# all_pcb.net
KiCad netlist of a schematic drawn in EasyEDA Pro
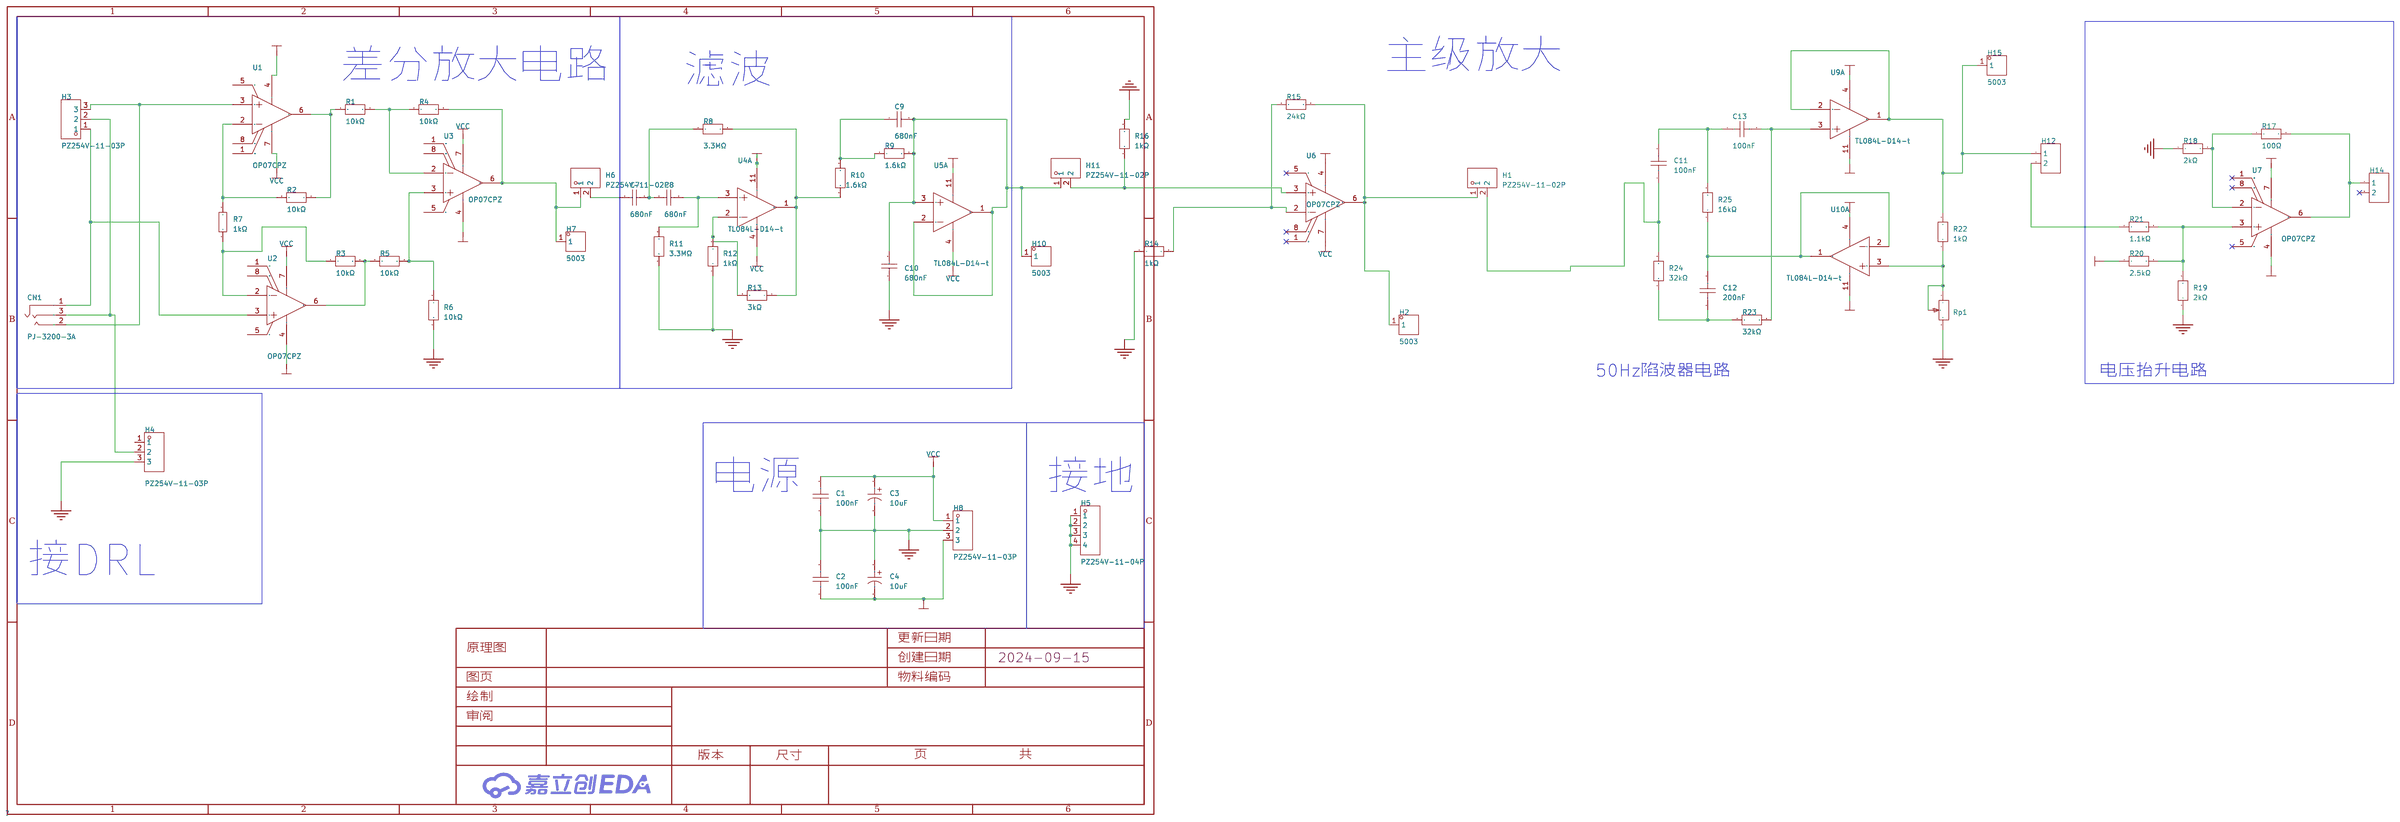
[diagram p0: schematic sheet]

(export (version "E")
  (design (tool "Eeschema 10.0.6"))
  (components
    (comp (ref "C1")
      (value "100nF")
      (footprint "easyedapro:CAP-TH_L13.0-W6.0-P10.0-D0.6")
      (description "容值:100nF;精度:±10%;电压(AC):275V;等级:X2;")
      (fields (field (name "Manufacturer Part") "1X2H410K275-11") (field (name "Manufacturer") "BM(丰明电容)"))
      (libsource (lib "easyedapro") (part "1X2H410K275-11"))
    )
    (comp (ref "C2")
      (value "100nF")
      (footprint "easyedapro:CAP-TH_L13.0-W6.0-P10.0-D0.6")
      (description "容值:100nF;精度:±10%;电压(AC):275V;等级:X2;")
      (fields (field (name "Manufacturer Part") "1X2H410K275-11") (field (name "Manufacturer") "BM(丰明电容)"))
      (libsource (lib "easyedapro") (part "1X2H410K275-11"))
    )
    (comp (ref "C3")
      (value "10uF")
      (footprint "easyedapro:CAP-TH_BD10.0-P5.00-D0.6-FD")
      (description "容值:10uF;精度:±20%;额定电压:250V;纹波电流:175mA@120Hz;等效串联电阻:-;")
      (fields
        (field (name "Manufacturer Part") "UCS2E100MPD1TD")
        (field (name "Manufacturer") "Nichicon(尼吉康)")
      )
      (libsource (lib "easyedapro") (part "UCS2E100MPD1TD"))
    )
    (comp (ref "C4")
      (value "10uF")
      (footprint "easyedapro:CAP-TH_BD10.0-P5.00-D0.6-FD")
      (description "容值:10uF;精度:±20%;额定电压:250V;纹波电流:175mA@120Hz;等效串联电阻:-;")
      (fields
        (field (name "Manufacturer Part") "UCS2E100MPD1TD")
        (field (name "Manufacturer") "Nichicon(尼吉康)")
      )
      (libsource (lib "easyedapro") (part "UCS2E100MPD1TD"))
    )
    (comp (ref "C7")
      (value "680nF")
      (footprint "easyedapro:CAP-TH_L7.5-W6.5-P5.00-D0.5")
      (description "容值:680nF;精度:±5%;额定电压:100V;工作温度:-40°C~+110°C;")
      (fields (field (name "Manufacturer Part") "PE684J2A0502") (field (name "Manufacturer") "KYET(科雅)"))
      (libsource (lib "easyedapro") (part "PE684J2A0502"))
    )
    (comp (ref "C8")
      (value "680nF")
      (footprint "easyedapro:CAP-TH_L7.5-W6.5-P5.00-D0.5")
      (description "容值:680nF;精度:±5%;额定电压:100V;工作温度:-40°C~+110°C;")
      (fields (field (name "Manufacturer Part") "PE684J2A0502") (field (name "Manufacturer") "KYET(科雅)"))
      (libsource (lib "easyedapro") (part "PE684J2A0502"))
    )
    (comp (ref "C9")
      (value "680nF")
      (footprint "easyedapro:CAP-TH_L7.5-W6.5-P5.00-D0.5")
      (description "容值:680nF;精度:±5%;额定电压:100V;工作温度:-40°C~+110°C;")
      (fields (field (name "Manufacturer Part") "PE684J2A0502") (field (name "Manufacturer") "KYET(科雅)"))
      (libsource (lib "easyedapro") (part "PE684J2A0502"))
    )
    (comp (ref "C10")
      (value "680nF")
      (footprint "easyedapro:CAP-TH_L7.5-W6.5-P5.00-D0.5")
      (description "容值:680nF;精度:±5%;额定电压:100V;工作温度:-40°C~+110°C;")
      (fields (field (name "Manufacturer Part") "PE684J2A0502") (field (name "Manufacturer") "KYET(科雅)"))
      (libsource (lib "easyedapro") (part "PE684J2A0502"))
    )
    (comp (ref "C11")
      (value "100nF")
      (footprint "easyedapro:CAP-TH_L5.1-W3.8-P5.08-D1.2")
      (description "容值:100nF;精度:±10%;额定电压:630V;温度系数:X7R;")
      (fields (field (name "Manufacturer Part") "C322C104KBR5TA") (field (name "Manufacturer") "KEMET(基美)"))
      (libsource (lib "easyedapro") (part "C322C104KBR5TA"))
    )
    (comp (ref "C12")
      (value "200nF")
      (footprint "easyedapro:CAP-TH_L18.0-W8.0-P15.00-D0.8")
      (description "容值:200nF;精度:±20%;电压(AC):305V;等级:X2;")
      (fields (field (name "Manufacturer Part") "B32922H3204M") (field (name "Manufacturer") "TDK"))
      (libsource (lib "easyedapro") (part "B32922H3204M"))
    )
    (comp (ref "C13")
      (value "100nF")
      (footprint "easyedapro:CAP-TH_L5.1-W3.8-P5.08-D1.2")
      (description "容值:100nF;精度:±10%;额定电压:630V;温度系数:X7R;")
      (fields (field (name "Manufacturer Part") "C322C104KBR5TA") (field (name "Manufacturer") "KEMET(基美)"))
      (libsource (lib "easyedapro") (part "C322C104KBR5TA"))
    )
    (comp (ref "CN1")
      (value "PJ-3200-3A")
      (footprint "easyedapro:AUDIO-TH_PJ-3200-3A")
      (description "连接器类型:3.5mm耳机座;额定电流:500mA;额定电压:30V;工作温度范围:-20°C~+70°C;")
      (fields (field (name "Manufacturer") "韩国韩荣"))
      (libsource (lib "easyedapro") (part "PJ-3200-3A"))
    )
    (comp (ref "H1")
      (value "PZ254V-11-02P")
      (footprint "easyedapro:HDR-TH_2P-P2.54-V-M")
      (fields (field (name "Manufacturer") "XFCN(兴飞)"))
      (libsource (lib "easyedapro") (part "PZ254V-11-02P"))
    )
    (comp (ref "H2")
      (value "5003")
      (footprint "easyedapro:TEST-TH_BD2.54-P1.39")
      (description "类型:测试环;全长/全高:7.62mm;工作高度:-;接触电阻:-;弹性寿命:-;额定电流:-;额定电压:-;触头材质:磷青铜;触头镀层:-;工作温度范围:-;")
      (fields (field (name "Manufacturer") "Keystone"))
      (libsource (lib "easyedapro") (part "5003"))
    )
    (comp (ref "H3")
      (value "PZ254V-11-03P")
      (footprint "easyedapro:HDR-TH_3P-P2.54-V-M")
      (fields (field (name "Manufacturer") "XFCN(兴飞)"))
      (libsource (lib "easyedapro") (part "PZ254V-11-03P_C2937625"))
    )
    (comp (ref "H4")
      (value "PZ254V-11-03P")
      (footprint "easyedapro:HDR-TH_3P-P2.54-V-M")
      (fields (field (name "Manufacturer") "XFCN(兴飞)"))
      (libsource (lib "easyedapro") (part "PZ254V-11-03P_C2937625"))
    )
    (comp (ref "H5")
      (value "PZ254V-11-04P")
      (footprint "easyedapro:HDR-TH_4P-P2.54-V-M")
      (fields (field (name "Manufacturer") "XFCN(兴飞)"))
      (libsource (lib "easyedapro") (part "PZ254V-11-04P_C2691448"))
    )
    (comp (ref "H6")
      (value "PZ254V-11-02P")
      (footprint "easyedapro:HDR-TH_2P-P2.54-V-M")
      (fields (field (name "Manufacturer") "XFCN(兴飞)"))
      (libsource (lib "easyedapro") (part "PZ254V-11-02P"))
    )
    (comp (ref "H7")
      (value "5003")
      (footprint "easyedapro:TEST-TH_BD2.54-P1.39")
      (description "类型:测试环;全长/全高:7.62mm;工作高度:-;接触电阻:-;弹性寿命:-;额定电流:-;额定电压:-;触头材质:磷青铜;触头镀层:-;工作温度范围:-;")
      (fields (field (name "Manufacturer") "Keystone"))
      (libsource (lib "easyedapro") (part "5003"))
    )
    (comp (ref "H8")
      (value "PZ254V-11-03P")
      (footprint "easyedapro:HDR-TH_3P-P2.54-V-M")
      (fields (field (name "Manufacturer") "XFCN(兴飞)"))
      (libsource (lib "easyedapro") (part "PZ254V-11-03P_C2937625"))
    )
    (comp (ref "H10")
      (value "5003")
      (footprint "easyedapro:TEST-TH_BD2.54-P1.39")
      (description "类型:测试环;全长/全高:7.62mm;工作高度:-;接触电阻:-;弹性寿命:-;额定电流:-;额定电压:-;触头材质:磷青铜;触头镀层:-;工作温度范围:-;")
      (fields (field (name "Manufacturer") "Keystone"))
      (libsource (lib "easyedapro") (part "5003"))
    )
    (comp (ref "H11")
      (value "PZ254V-11-02P")
      (footprint "easyedapro:HDR-TH_2P-P2.54-V-M")
      (fields (field (name "Manufacturer") "XFCN(兴飞)"))
      (libsource (lib "easyedapro") (part "PZ254V-11-02P"))
    )
    (comp (ref "H12")
      (value "~")
      (footprint "easyedapro:HDR-TH_2P-P2.54-V-F")
      (libsource (lib "easyedapro") (part "Header-Female-2.54_1x2"))
    )
    (comp (ref "H14")
      (value "~")
      (footprint "easyedapro:HDR-TH_2P-P2.54-V-F")
      (libsource (lib "easyedapro") (part "Header-Female-2.54_1x2"))
    )
    (comp (ref "H15")
      (value "5003")
      (footprint "easyedapro:TEST-TH_BD2.54-P1.39")
      (description "类型:测试环;全长/全高:7.62mm;工作高度:-;接触电阻:-;弹性寿命:-;额定电流:-;额定电压:-;触头材质:磷青铜;触头镀层:-;工作温度范围:-;")
      (fields (field (name "Manufacturer") "Keystone"))
      (libsource (lib "easyedapro") (part "5003"))
    )
    (comp (ref "R1")
      (value "10kΩ")
      (footprint "easyedapro:RES-TH_BD2.4-L6.3-P10.30-D0.6")
      (description "电阻类型:金属膜电阻;阻值:10kΩ;精度:±1%;功率:250mW;温度系数:±50ppm/°C;")
      (fields
        (field (name "Manufacturer Part") "RN1/4W10KFT/BA1")
        (field (name "Manufacturer") "Tyohm(幸亚电阻)")
      )
      (libsource (lib "easyedapro") (part "RN 1/4W 10K F T/B A1"))
    )
    (comp (ref "R2")
      (value "10kΩ")
      (footprint "easyedapro:RES-TH_BD2.4-L6.3-P10.30-D0.6")
      (description "电阻类型:金属膜电阻;阻值:10kΩ;精度:±1%;功率:250mW;温度系数:±50ppm/°C;")
      (fields
        (field (name "Manufacturer Part") "RN1/4W10KFT/BA1")
        (field (name "Manufacturer") "Tyohm(幸亚电阻)")
      )
      (libsource (lib "easyedapro") (part "RN 1/4W 10K F T/B A1"))
    )
    (comp (ref "R3")
      (value "10kΩ")
      (footprint "easyedapro:RES-TH_BD2.4-L6.3-P10.30-D0.6")
      (description "电阻类型:金属膜电阻;阻值:10kΩ;精度:±1%;功率:250mW;温度系数:±50ppm/°C;")
      (fields
        (field (name "Manufacturer Part") "RN1/4W10KFT/BA1")
        (field (name "Manufacturer") "Tyohm(幸亚电阻)")
      )
      (libsource (lib "easyedapro") (part "RN 1/4W 10K F T/B A1"))
    )
    (comp (ref "R4")
      (value "10kΩ")
      (footprint "easyedapro:RES-TH_BD2.4-L6.3-P10.30-D0.6")
      (description "电阻类型:金属膜电阻;阻值:10kΩ;精度:±1%;功率:250mW;温度系数:±50ppm/°C;")
      (fields
        (field (name "Manufacturer Part") "RN1/4W10KFT/BA1")
        (field (name "Manufacturer") "Tyohm(幸亚电阻)")
      )
      (libsource (lib "easyedapro") (part "RN 1/4W 10K F T/B A1"))
    )
    (comp (ref "R5")
      (value "10kΩ")
      (footprint "easyedapro:RES-TH_BD2.4-L6.3-P10.30-D0.6")
      (description "电阻类型:金属膜电阻;阻值:10kΩ;精度:±1%;功率:250mW;温度系数:±50ppm/°C;")
      (fields
        (field (name "Manufacturer Part") "RN1/4W10KFT/BA1")
        (field (name "Manufacturer") "Tyohm(幸亚电阻)")
      )
      (libsource (lib "easyedapro") (part "RN 1/4W 10K F T/B A1"))
    )
    (comp (ref "R6")
      (value "10kΩ")
      (footprint "easyedapro:RES-TH_BD2.4-L6.3-P10.30-D0.6")
      (description "电阻类型:金属膜电阻;阻值:10kΩ;精度:±1%;功率:250mW;温度系数:±50ppm/°C;")
      (fields
        (field (name "Manufacturer Part") "RN1/4W10KFT/BA1")
        (field (name "Manufacturer") "Tyohm(幸亚电阻)")
      )
      (libsource (lib "easyedapro") (part "RN 1/4W 10K F T/B A1"))
    )
    (comp (ref "R7")
      (value "1kΩ")
      (footprint "easyedapro:RES-TH_BD2.5-L6.5-P10.50-D0.6")
      (description "电阻类型:金属膜电阻;阻值:1kΩ;精度:±1%;功率:250mW;温度系数:±50ppm/°C;")
      (fields
        (field (name "Manufacturer Part") "MFR0W4F1001A50")
        (field (name "Manufacturer") "UNI-ROYAL(厚声)")
      )
      (libsource (lib "easyedapro") (part "MFR0W4F1001A50"))
    )
    (comp (ref "R8")
      (value "3.3MΩ")
      (footprint "easyedapro:RES-TH_BD2.4-L6.3-P10.30-D0.6")
      (description "电阻类型:金属膜电阻;阻值:10kΩ;精度:±1%;功率:250mW;温度系数:±50ppm/°C;")
      (fields
        (field (name "Manufacturer Part") "RN1/4W10KFT/BA1")
        (field (name "Manufacturer") "Tyohm(幸亚电阻)")
      )
      (libsource (lib "easyedapro") (part "RN 1/4W 10K F T/B A1"))
    )
    (comp (ref "R9")
      (value "1.6kΩ")
      (footprint "easyedapro:RES-TH_BD2.4-L6.3-P10.30-D0.6")
      (description "电阻类型:金属膜电阻;阻值:10kΩ;精度:±1%;功率:250mW;温度系数:±50ppm/°C;")
      (fields
        (field (name "Manufacturer Part") "RN1/4W10KFT/BA1")
        (field (name "Manufacturer") "Tyohm(幸亚电阻)")
      )
      (libsource (lib "easyedapro") (part "RN 1/4W 10K F T/B A1"))
    )
    (comp (ref "R10")
      (value "1.6kΩ")
      (footprint "easyedapro:RES-TH_BD2.4-L6.3-P10.30-D0.6")
      (description "电阻类型:金属膜电阻;阻值:10kΩ;精度:±1%;功率:250mW;温度系数:±50ppm/°C;")
      (fields
        (field (name "Manufacturer Part") "RN1/4W10KFT/BA1")
        (field (name "Manufacturer") "Tyohm(幸亚电阻)")
      )
      (libsource (lib "easyedapro") (part "RN 1/4W 10K F T/B A1"))
    )
    (comp (ref "R11")
      (value "3.3MΩ")
      (footprint "easyedapro:RES-TH_BD2.4-L6.3-P10.30-D0.6")
      (description "电阻类型:金属膜电阻;阻值:10kΩ;精度:±1%;功率:250mW;温度系数:±50ppm/°C;")
      (fields
        (field (name "Manufacturer Part") "RN1/4W10KFT/BA1")
        (field (name "Manufacturer") "Tyohm(幸亚电阻)")
      )
      (libsource (lib "easyedapro") (part "RN 1/4W 10K F T/B A1"))
    )
    (comp (ref "R12")
      (value "1kΩ")
      (footprint "easyedapro:RES-TH_BD2.4-L6.3-P10.30-D0.6")
      (description "电阻类型:金属膜电阻;阻值:10kΩ;精度:±1%;功率:250mW;温度系数:±50ppm/°C;")
      (fields
        (field (name "Manufacturer Part") "RN1/4W10KFT/BA1")
        (field (name "Manufacturer") "Tyohm(幸亚电阻)")
      )
      (libsource (lib "easyedapro") (part "RN 1/4W 10K F T/B A1"))
    )
    (comp (ref "R13")
      (value "3kΩ")
      (footprint "easyedapro:RES-TH_BD2.4-L6.3-P10.30-D0.6")
      (description "电阻类型:金属膜电阻;阻值:10kΩ;精度:±1%;功率:250mW;温度系数:±50ppm/°C;")
      (fields
        (field (name "Manufacturer Part") "RN1/4W10KFT/BA1")
        (field (name "Manufacturer") "Tyohm(幸亚电阻)")
      )
      (libsource (lib "easyedapro") (part "RN 1/4W 10K F T/B A1"))
    )
    (comp (ref "R14")
      (value "1kΩ")
      (footprint "easyedapro:RES-TH_BD2.4-L6.3-P10.30-D0.6")
      (description "电阻类型:金属膜电阻;阻值:10kΩ;精度:±1%;功率:250mW;温度系数:±50ppm/°C;")
      (fields
        (field (name "Manufacturer Part") "RN1/4W10KFT/BA1")
        (field (name "Manufacturer") "Tyohm(幸亚电阻)")
      )
      (libsource (lib "easyedapro") (part "RN 1/4W 10K F T/B A1"))
    )
    (comp (ref "R15")
      (value "24kΩ")
      (footprint "easyedapro:RES-TH_BD2.4-L6.3-P10.30-D0.6")
      (description "电阻类型:金属膜电阻;阻值:10kΩ;精度:±1%;功率:250mW;温度系数:±50ppm/°C;")
      (fields
        (field (name "Manufacturer Part") "RN1/4W10KFT/BA1")
        (field (name "Manufacturer") "Tyohm(幸亚电阻)")
      )
      (libsource (lib "easyedapro") (part "RN 1/4W 10K F T/B A1"))
    )
    (comp (ref "R16")
      (value "1kΩ")
      (footprint "easyedapro:RES-TH_BD2.4-L6.3-P10.30-D0.6")
      (description "电阻类型:金属膜电阻;阻值:10kΩ;精度:±1%;功率:250mW;温度系数:±50ppm/°C;")
      (fields
        (field (name "Manufacturer Part") "RN1/4W10KFT/BA1")
        (field (name "Manufacturer") "Tyohm(幸亚电阻)")
      )
      (libsource (lib "easyedapro") (part "RN 1/4W 10K F T/B A1"))
    )
    (comp (ref "R17")
      (value "100Ω")
      (footprint "easyedapro:RES-TH_BD3.7-L10.0-P15.00-D0.6")
      (description "电阻类型:金属膜电阻;阻值:100Ω;精度:±0.1%;功率:500mW;温度系数:±5ppm/°C;")
      (fields (field (name "Manufacturer Part") "MMFR3710B100RV9") (field (name "Manufacturer") "RESI(开步睿思)"))
      (libsource (lib "easyedapro") (part "MMFR3710B100RV9"))
    )
    (comp (ref "R18")
      (value "2kΩ")
      (footprint "easyedapro:RES-TH_BD2.3-L6.5-P10.50-D0.5")
      (description "电阻类型:金属膜电阻;阻值:2kΩ;精度:±1%;功率:250mW;温度系数:±200ppm/°C;")
      (fields (field (name "Manufacturer Part") "MF1/4W-2KΩ±1%T52") (field (name "Manufacturer") "华星机电"))
      (libsource (lib "easyedapro") (part "MF1/4W-2KΩ±1%T52"))
    )
    (comp (ref "R19")
      (value "2kΩ")
      (footprint "easyedapro:RES-TH_BD2.3-L6.5-P10.50-D0.5")
      (description "电阻类型:金属膜电阻;阻值:2kΩ;精度:±1%;功率:250mW;温度系数:±200ppm/°C;")
      (fields (field (name "Manufacturer Part") "MF1/4W-2KΩ±1%T52") (field (name "Manufacturer") "华星机电"))
      (libsource (lib "easyedapro") (part "MF1/4W-2KΩ±1%T52"))
    )
    (comp (ref "R20")
      (value "2.5kΩ")
      (footprint "easyedapro:RES-TH_BD4.6-L11.4-P15.40-D0.8")
      (description "电阻类型:绕线电阻;阻值:2.5kΩ;精度:±1%;功率:2W;温度系数:±20ppm/°C;")
      (fields (field (name "Manufacturer Part") "WHC2K5FET") (field (name "Manufacturer") "Ohmite"))
      (libsource (lib "easyedapro") (part "WHC2K5FET"))
    )
    (comp (ref "R21")
      (value "1.1kΩ")
      (footprint "easyedapro:RES-TH_BD3.3-L9.0-P13.00-D0.6")
      (description "电阻类型:金属膜电阻;阻值:1.1kΩ;精度:±5%;功率:500mW;温度系数:±300ppm/°C;")
      (fields (field (name "Manufacturer Part") "RSF-50JR-52-1K1") (field (name "Manufacturer") "YAGEO(国巨)"))
      (libsource (lib "easyedapro") (part "RSF-50JR-52-1K1"))
    )
    (comp (ref "R22")
      (value "1kΩ")
      (footprint "easyedapro:RES-TH_BD2.3-L6.5-P10.50-D0.5")
      (description "电阻类型:金属膜电阻;阻值:5.1kΩ;精度:±1%;功率:250mW;温度系数:±200ppm/°C;")
      (fields (field (name "Manufacturer Part") "MF1/4W-5.1KΩ±1%T52") (field (name "Manufacturer") "华星机电"))
      (libsource (lib "easyedapro") (part "MF1/4W-5.1KΩ±1%T52"))
    )
    (comp (ref "R23")
      (value "32kΩ")
      (footprint "easyedapro:RES-TH_BD2.4-L6.5-P10.50-D0.5")
      (description "电阻类型:金属膜电阻;阻值:32kΩ;精度:±0.1%;功率:250mW;温度系数:±25ppm/°C;")
      (fields
        (field (name "Manufacturer Part") "RNF14BTE32K0")
        (field (name "Manufacturer") "SEI(Stackpole Electronics Inc.)")
      )
      (libsource (lib "easyedapro") (part "RNF14BTE32K0"))
    )
    (comp (ref "R24")
      (value "32kΩ")
      (footprint "easyedapro:RES-TH_BD2.4-L6.5-P10.50-D0.5")
      (description "电阻类型:金属膜电阻;阻值:32kΩ;精度:±0.1%;功率:250mW;温度系数:±25ppm/°C;")
      (fields
        (field (name "Manufacturer Part") "RNF14BTE32K0")
        (field (name "Manufacturer") "SEI(Stackpole Electronics Inc.)")
      )
      (libsource (lib "easyedapro") (part "RNF14BTE32K0"))
    )
    (comp (ref "R25")
      (value "16kΩ")
      (footprint "easyedapro:RES-TH_BD3.3-L9.0-P13.00-D0.6")
      (description "电阻类型:金属膜电阻;阻值:16kΩ;精度:±5%;功率:500mW;温度系数:±300ppm/°C;")
      (fields (field (name "Manufacturer Part") "RSF-50JT-52-16K") (field (name "Manufacturer") "YAGEO(国巨)"))
      (libsource (lib "easyedapro") (part "RSF-50JT-52-16K"))
    )
    (comp (ref "Rp1")
      (value "-")
      (footprint "easyedapro:RES-ADJ-TH_3296W")
      (description "阻值:-;功率:-;")
      (fields (field (name "Manufacturer Part") "精密电位器 3296W/50欧姆"))
      (libsource (lib "easyedapro") (part "Precision potentiometer 3296W/50ohm"))
    )
    (comp (ref "U1")
      (value "OP07CPZ")
      (footprint "easyedapro:PDIP-8_L9.3-W6.4-P2.54-LS7.6-BL")
      (description "超低失调电压运算放大器")
      (fields (field (name "Manufacturer") "ADI(亚德诺)"))
      (libsource (lib "easyedapro") (part "OP07CPZ"))
    )
    (comp (ref "U2")
      (value "OP07CPZ")
      (footprint "easyedapro:PDIP-8_L9.3-W6.4-P2.54-LS7.6-BL")
      (description "超低失调电压运算放大器")
      (fields (field (name "Manufacturer") "ADI(亚德诺)"))
      (libsource (lib "easyedapro") (part "OP07CPZ"))
    )
    (comp (ref "U3")
      (value "OP07CPZ")
      (footprint "easyedapro:PDIP-8_L9.3-W6.4-P2.54-LS7.6-BL")
      (description "超低失调电压运算放大器")
      (fields (field (name "Manufacturer") "ADI(亚德诺)"))
      (libsource (lib "easyedapro") (part "OP07CPZ"))
    )
    (comp (ref "U4")
      (value "TL084L-D14-t")
      (footprint "easyedapro:PDIP-14_L19.3-W6.5-P2.54-LS7.6-BL")
      (fields (field (name "Manufacturer") "UTC(友顺)"))
      (libsource (lib "easyedapro") (part "TL084L"))
    )
    (comp (ref "U5")
      (value "TL084L-D14-t")
      (footprint "easyedapro:PDIP-14_L19.3-W6.5-P2.54-LS7.6-BL")
      (fields (field (name "Manufacturer") "UTC(友顺)"))
      (libsource (lib "easyedapro") (part "TL084L"))
    )
    (comp (ref "U6")
      (value "OP07CPZ")
      (footprint "easyedapro:PDIP-8_L9.3-W6.4-P2.54-LS7.6-BL")
      (description "超低失调电压运算放大器")
      (fields (field (name "Manufacturer") "ADI(亚德诺)"))
      (libsource (lib "easyedapro") (part "OP07CPZ"))
    )
    (comp (ref "U7")
      (value "OP07CPZ")
      (footprint "easyedapro:PDIP-8_L9.3-W6.4-P2.54-LS7.6-BL")
      (description "超低失调电压运算放大器")
      (fields (field (name "Manufacturer") "ADI(亚德诺)"))
      (libsource (lib "easyedapro") (part "OP07CPZ"))
    )
    (comp (ref "U9")
      (value "TL084L-D14-t")
      (footprint "easyedapro:PDIP-14_L19.3-W6.5-P2.54-LS7.6-BL")
      (fields (field (name "Manufacturer") "UTC(友顺)"))
      (libsource (lib "easyedapro") (part "TL084L"))
    )
    (comp (ref "U10")
      (value "TL084L-D14-t")
      (footprint "easyedapro:PDIP-14_L19.3-W6.5-P2.54-LS7.6-BL")
      (fields (field (name "Manufacturer") "UTC(友顺)"))
      (libsource (lib "easyedapro") (part "TL084L"))
    )
  )
  (nets
    (net (code "1") (name "GND") (class "Default")
      (node (ref "C1") (pin "1") (pinfunction "1_1") (pintype "unspecified"))
      (node (ref "C10") (pin "1") (pinfunction "1_1") (pintype "input"))
      (node (ref "C2") (pin "2") (pinfunction "2_2") (pintype "unspecified"))
      (node (ref "C3") (pin "2") (pinfunction "2_2") (pintype "input"))
      (node (ref "C4") (pin "1") (pinfunction "1_1") (pintype "input"))
      (node (ref "H4") (pin "3") (pinfunction "3_3") (pintype "unspecified"))
      (node (ref "H5") (pin "1") (pinfunction "1_1") (pintype "unspecified"))
      (node (ref "H5") (pin "2") (pinfunction "2_2") (pintype "unspecified"))
      (node (ref "H5") (pin "3") (pinfunction "3_3") (pintype "unspecified"))
      (node (ref "H5") (pin "4") (pinfunction "4_4") (pintype "unspecified"))
      (node (ref "H8") (pin "2") (pinfunction "2_2") (pintype "unspecified"))
      (node (ref "R11") (pin "1") (pinfunction "1_1") (pintype "unspecified"))
      (node (ref "R12") (pin "1") (pinfunction "1_1") (pintype "unspecified"))
      (node (ref "R14") (pin "1") (pinfunction "1_1") (pintype "unspecified"))
      (node (ref "R16") (pin "2") (pinfunction "2_2") (pintype "unspecified"))
      (node (ref "R18") (pin "1") (pinfunction "1_1") (pintype "unspecified"))
      (node (ref "R19") (pin "1") (pinfunction "1_1") (pintype "unspecified"))
      (node (ref "R6") (pin "1") (pinfunction "1_1") (pintype "unspecified"))
      (node (ref "Rp1") (pin "3") (pinfunction "3_3") (pintype "input"))
    )
    (net (code "2") (name "Net-(C7-Pad1)") (class "Default")
      (node (ref "C7") (pin "1") (pinfunction "1_1") (pintype "input"))
      (node (ref "H6") (pin "2") (pinfunction "2_2") (pintype "unspecified"))
    )
    (net (code "3") (name "Net-(C7-Pad2)") (class "Default")
      (node (ref "C7") (pin "2") (pinfunction "2_2") (pintype "input"))
      (node (ref "C8") (pin "1") (pinfunction "1_1") (pintype "input"))
      (node (ref "R8") (pin "1") (pinfunction "1_1") (pintype "unspecified"))
    )
    (net (code "4") (name "Net-(C9-Pad1)") (class "Default")
      (node (ref "C9") (pin "1") (pinfunction "1_1") (pintype "input"))
      (node (ref "R10") (pin "2") (pinfunction "2_2") (pintype "unspecified"))
      (node (ref "R9") (pin "1") (pinfunction "1_1") (pintype "unspecified"))
    )
    (net (code "5") (name "Net-(C11-Pad1)") (class "Default")
      (node (ref "C11") (pin "1") (pinfunction "1_1") (pintype "unspecified"))
      (node (ref "H1") (pin "2") (pinfunction "2_2") (pintype "unspecified"))
      (node (ref "R24") (pin "2") (pinfunction "2_2") (pintype "unspecified"))
    )
    (net (code "6") (name "Net-(C11-Pad2)") (class "Default")
      (node (ref "C11") (pin "2") (pinfunction "2_2") (pintype "unspecified"))
      (node (ref "C13") (pin "1") (pinfunction "1_1") (pintype "unspecified"))
      (node (ref "R25") (pin "2") (pinfunction "2_2") (pintype "unspecified"))
    )
    (net (code "7") (name "Net-(C12-Pad1)") (class "Default")
      (node (ref "C12") (pin "1") (pinfunction "1_1") (pintype "unspecified"))
      (node (ref "R23") (pin "1") (pinfunction "1_1") (pintype "unspecified"))
      (node (ref "R24") (pin "1") (pinfunction "1_1") (pintype "unspecified"))
    )
    (net (code "8") (name "Net-(CN1-Pad3)") (class "Default")
      (node (ref "CN1") (pin "3") (pinfunction "3_3") (pintype "unspecified"))
      (node (ref "H3") (pin "2") (pinfunction "2_2") (pintype "unspecified"))
      (node (ref "H4") (pin "2") (pinfunction "2_2") (pintype "unspecified"))
    )
    (net (code "9") (name "Net-(H12-Pad2)") (class "Default")
      (node (ref "H12") (pin "2") (pinfunction "2_2") (pintype "input"))
      (node (ref "R21") (pin "1") (pinfunction "1_1") (pintype "input"))
    )
    (net (code "10") (name "Net-(U1-IN+)") (class "Default")
      (node (ref "CN1") (pin "2") (pinfunction "2_2") (pintype "unspecified"))
      (node (ref "H3") (pin "3") (pinfunction "3_3") (pintype "unspecified"))
      (node (ref "U1") (pin "3") (pinfunction "IN+_3") (pintype "unspecified"))
    )
    (net (code "11") (name "Net-(U1-IN-)") (class "Default")
      (node (ref "R2") (pin "2") (pinfunction "2_2") (pintype "unspecified"))
      (node (ref "R7") (pin "2") (pinfunction "2_2") (pintype "input"))
      (node (ref "U1") (pin "2") (pinfunction "IN-_2") (pintype "unspecified"))
    )
    (net (code "12") (name "Net-(U1-OUT)") (class "Default")
      (node (ref "R1") (pin "1") (pinfunction "1_1") (pintype "unspecified"))
      (node (ref "R2") (pin "1") (pinfunction "1_1") (pintype "unspecified"))
      (node (ref "U1") (pin "6") (pinfunction "OUT_6") (pintype "output"))
    )
    (net (code "13") (name "Net-(U2-IN+)") (class "Default")
      (node (ref "CN1") (pin "1") (pinfunction "1_1") (pintype "unspecified"))
      (node (ref "H3") (pin "1") (pinfunction "1_1") (pintype "unspecified"))
      (node (ref "U2") (pin "3") (pinfunction "IN+_3") (pintype "unspecified"))
    )
    (net (code "14") (name "Net-(U2-IN-)") (class "Default")
      (node (ref "R3") (pin "1") (pinfunction "1_1") (pintype "unspecified"))
      (node (ref "R7") (pin "1") (pinfunction "1_1") (pintype "input"))
      (node (ref "U2") (pin "2") (pinfunction "IN-_2") (pintype "unspecified"))
    )
    (net (code "15") (name "Net-(U2-OUT)") (class "Default")
      (node (ref "R3") (pin "2") (pinfunction "2_2") (pintype "unspecified"))
      (node (ref "R5") (pin "1") (pinfunction "1_1") (pintype "unspecified"))
      (node (ref "U2") (pin "6") (pinfunction "OUT_6") (pintype "output"))
    )
    (net (code "16") (name "Net-(U3-IN+)") (class "Default")
      (node (ref "R5") (pin "2") (pinfunction "2_2") (pintype "unspecified"))
      (node (ref "R6") (pin "2") (pinfunction "2_2") (pintype "unspecified"))
      (node (ref "U3") (pin "3") (pinfunction "IN+_3") (pintype "unspecified"))
    )
    (net (code "17") (name "Net-(U3-IN-)") (class "Default")
      (node (ref "R1") (pin "2") (pinfunction "2_2") (pintype "unspecified"))
      (node (ref "R4") (pin "1") (pinfunction "1_1") (pintype "unspecified"))
      (node (ref "U3") (pin "2") (pinfunction "IN-_2") (pintype "unspecified"))
    )
    (net (code "18") (name "Net-(U3-OUT)") (class "Default")
      (node (ref "H6") (pin "1") (pinfunction "1_1") (pintype "unspecified"))
      (node (ref "H7") (pin "1") (pinfunction "1_1") (pintype "unspecified"))
      (node (ref "R4") (pin "2") (pinfunction "2_2") (pintype "unspecified"))
      (node (ref "U3") (pin "6") (pinfunction "OUT_6") (pintype "output"))
    )
    (net (code "19") (name "Net-(U4A-IN1+)") (class "Default")
      (node (ref "C8") (pin "2") (pinfunction "2_2") (pintype "input"))
      (node (ref "R11") (pin "2") (pinfunction "2_2") (pintype "unspecified"))
      (node (ref "U4") (pin "3") (pinfunction "IN1+_3") (pintype "unspecified"))
    )
    (net (code "20") (name "Net-(U4A-IN1-)") (class "Default")
      (node (ref "R12") (pin "2") (pinfunction "2_2") (pintype "unspecified"))
      (node (ref "R13") (pin "2") (pinfunction "2_2") (pintype "unspecified"))
      (node (ref "U4") (pin "2") (pinfunction "IN1-_2") (pintype "unspecified"))
    )
    (net (code "21") (name "Net-(U4A-OUT1)") (class "Default")
      (node (ref "R10") (pin "1") (pinfunction "1_1") (pintype "unspecified"))
      (node (ref "R13") (pin "1") (pinfunction "1_1") (pintype "unspecified"))
      (node (ref "R8") (pin "2") (pinfunction "2_2") (pintype "unspecified"))
      (node (ref "U4") (pin "1") (pinfunction "OUT1_1") (pintype "output"))
    )
    (net (code "22") (name "Net-(U5A-IN1+)") (class "Default")
      (node (ref "C10") (pin "2") (pinfunction "2_2") (pintype "input"))
      (node (ref "C9") (pin "2") (pinfunction "2_2") (pintype "input"))
      (node (ref "H10") (pin "1") (pinfunction "1_1") (pintype "unspecified"))
      (node (ref "H11") (pin "1") (pinfunction "1_1") (pintype "unspecified"))
      (node (ref "R9") (pin "2") (pinfunction "2_2") (pintype "unspecified"))
      (node (ref "U5") (pin "1") (pinfunction "OUT1_1") (pintype "output"))
      (node (ref "U5") (pin "2") (pinfunction "IN1-_2") (pintype "unspecified"))
      (node (ref "U5") (pin "3") (pinfunction "IN1+_3") (pintype "unspecified"))
    )
    (net (code "23") (name "Net-(U6-IN+)") (class "Default")
      (node (ref "H11") (pin "2") (pinfunction "2_2") (pintype "unspecified"))
      (node (ref "R16") (pin "1") (pinfunction "1_1") (pintype "unspecified"))
      (node (ref "U6") (pin "3") (pinfunction "IN+_3") (pintype "unspecified"))
    )
    (net (code "24") (name "Net-(U6-IN-)") (class "Default")
      (node (ref "R14") (pin "2") (pinfunction "2_2") (pintype "unspecified"))
      (node (ref "R15") (pin "1") (pinfunction "1_1") (pintype "unspecified"))
      (node (ref "U6") (pin "2") (pinfunction "IN-_2") (pintype "unspecified"))
    )
    (net (code "25") (name "Net-(U6-OUT)") (class "Default")
      (node (ref "H1") (pin "1") (pinfunction "1_1") (pintype "unspecified"))
      (node (ref "H2") (pin "1") (pinfunction "1_1") (pintype "unspecified"))
      (node (ref "R15") (pin "2") (pinfunction "2_2") (pintype "unspecified"))
      (node (ref "U6") (pin "6") (pinfunction "OUT_6") (pintype "output"))
    )
    (net (code "26") (name "Net-(U7-IN+)") (class "Default")
      (node (ref "R19") (pin "2") (pinfunction "2_2") (pintype "unspecified"))
      (node (ref "R20") (pin "2") (pinfunction "2_2") (pintype "unspecified"))
      (node (ref "R21") (pin "2") (pinfunction "2_2") (pintype "input"))
      (node (ref "U7") (pin "3") (pinfunction "IN+_3") (pintype "unspecified"))
    )
    (net (code "27") (name "Net-(U7-IN-)") (class "Default")
      (node (ref "R17") (pin "1") (pinfunction "1_1") (pintype "unspecified"))
      (node (ref "R18") (pin "2") (pinfunction "2_2") (pintype "unspecified"))
      (node (ref "U7") (pin "2") (pinfunction "IN-_2") (pintype "unspecified"))
    )
    (net (code "28") (name "Net-(U7-OUT)") (class "Default")
      (node (ref "H14") (pin "1") (pinfunction "1_1") (pintype "input"))
      (node (ref "R17") (pin "2") (pinfunction "2_2") (pintype "unspecified"))
      (node (ref "U7") (pin "6") (pinfunction "OUT_6") (pintype "output"))
    )
    (net (code "29") (name "Net-(U9A-IN1+)") (class "Default")
      (node (ref "C13") (pin "2") (pinfunction "2_2") (pintype "unspecified"))
      (node (ref "R23") (pin "2") (pinfunction "2_2") (pintype "unspecified"))
      (node (ref "U9") (pin "3") (pinfunction "IN1+_3") (pintype "unspecified"))
    )
    (net (code "30") (name "Net-(U9A-IN1-)") (class "Default")
      (node (ref "H12") (pin "1") (pinfunction "1_1") (pintype "input"))
      (node (ref "H15") (pin "1") (pinfunction "1_1") (pintype "unspecified"))
      (node (ref "R22") (pin "2") (pinfunction "2_2") (pintype "unspecified"))
      (node (ref "U9") (pin "1") (pinfunction "OUT1_1") (pintype "output"))
      (node (ref "U9") (pin "2") (pinfunction "IN1-_2") (pintype "unspecified"))
    )
    (net (code "31") (name "Net-(U10A-IN1+)") (class "Default")
      (node (ref "R22") (pin "1") (pinfunction "1_1") (pintype "unspecified"))
      (node (ref "Rp1") (pin "1") (pinfunction "1_1") (pintype "input"))
      (node (ref "Rp1") (pin "2") (pinfunction "2_2") (pintype "input"))
      (node (ref "U10") (pin "3") (pinfunction "IN1+_3") (pintype "unspecified"))
    )
    (net (code "32") (name "Net-(U10A-IN1-)") (class "Default")
      (node (ref "C12") (pin "2") (pinfunction "2_2") (pintype "unspecified"))
      (node (ref "R25") (pin "1") (pinfunction "1_1") (pintype "unspecified"))
      (node (ref "U10") (pin "1") (pinfunction "OUT1_1") (pintype "output"))
      (node (ref "U10") (pin "2") (pinfunction "IN1-_2") (pintype "unspecified"))
    )
    (net (code "33") (name "VCC") (class "Default")
      (node (ref "C1") (pin "2") (pinfunction "2_2") (pintype "unspecified"))
      (node (ref "C3") (pin "1") (pinfunction "1_1") (pintype "input"))
      (node (ref "H8") (pin "1") (pinfunction "1_1") (pintype "unspecified"))
      (node (ref "R20") (pin "1") (pinfunction "1_1") (pintype "unspecified"))
      (node (ref "U1") (pin "7") (pinfunction "V+_7") (pintype "unspecified"))
      (node (ref "U10") (pin "4") (pinfunction "V+_4") (pintype "unspecified"))
      (node (ref "U2") (pin "7") (pinfunction "V+_7") (pintype "unspecified"))
      (node (ref "U3") (pin "7") (pinfunction "V+_7") (pintype "unspecified"))
      (node (ref "U4") (pin "4") (pinfunction "V+_4") (pintype "unspecified"))
      (node (ref "U5") (pin "4") (pinfunction "V+_4") (pintype "unspecified"))
      (node (ref "U6") (pin "7") (pinfunction "V+_7") (pintype "unspecified"))
      (node (ref "U7") (pin "7") (pinfunction "V+_7") (pintype "unspecified"))
      (node (ref "U9") (pin "4") (pinfunction "V+_4") (pintype "unspecified"))
    )
    (net (code "34") (name "VEE") (class "Default")
      (node (ref "C2") (pin "1") (pinfunction "1_1") (pintype "unspecified"))
      (node (ref "C4") (pin "2") (pinfunction "2_2") (pintype "input"))
      (node (ref "H8") (pin "3") (pinfunction "3_3") (pintype "unspecified"))
      (node (ref "U1") (pin "4") (pinfunction "V-_4") (pintype "unspecified"))
      (node (ref "U10") (pin "11") (pinfunction "V-_11") (pintype "unspecified"))
      (node (ref "U2") (pin "4") (pinfunction "V-_4") (pintype "unspecified"))
      (node (ref "U3") (pin "4") (pinfunction "V-_4") (pintype "unspecified"))
      (node (ref "U4") (pin "11") (pinfunction "V-_11") (pintype "unspecified"))
      (node (ref "U5") (pin "11") (pinfunction "V-_11") (pintype "unspecified"))
      (node (ref "U6") (pin "4") (pinfunction "V-_4") (pintype "unspecified"))
      (node (ref "U7") (pin "4") (pinfunction "V-_4") (pintype "unspecified"))
      (node (ref "U9") (pin "11") (pinfunction "V-_11") (pintype "unspecified"))
    )
    (net (code "35") (name "unconnected-(H4-Pad1)") (class "Default")
      (node (ref "H4") (pin "1") (pinfunction "1_1") (pintype "unspecified"))
    )
    (net (code "36") (name "unconnected-(H14-Pad2)") (class "Default")
      (node (ref "H14") (pin "2") (pinfunction "2_2") (pintype "input+no_connect"))
    )
    (net (code "37") (name "unconnected-(U1-NC-Pad5)") (class "Default")
      (node (ref "U1") (pin "5") (pinfunction "NC_5") (pintype "unspecified"))
    )
    (net (code "38") (name "unconnected-(U1-VOS_TRIM-Pad1)") (class "Default")
      (node (ref "U1") (pin "1") (pinfunction "VOS_TRIM_1") (pintype "unspecified"))
    )
    (net (code "39") (name "unconnected-(U1-VOS_TRIM-Pad8)") (class "Default")
      (node (ref "U1") (pin "8") (pinfunction "VOS_TRIM_8") (pintype "unspecified"))
    )
    (net (code "40") (name "unconnected-(U2-NC-Pad5)") (class "Default")
      (node (ref "U2") (pin "5") (pinfunction "NC_5") (pintype "unspecified"))
    )
    (net (code "41") (name "unconnected-(U2-VOS_TRIM-Pad1)") (class "Default")
      (node (ref "U2") (pin "1") (pinfunction "VOS_TRIM_1") (pintype "unspecified"))
    )
    (net (code "42") (name "unconnected-(U2-VOS_TRIM-Pad8)") (class "Default")
      (node (ref "U2") (pin "8") (pinfunction "VOS_TRIM_8") (pintype "unspecified"))
    )
    (net (code "43") (name "unconnected-(U3-NC-Pad5)") (class "Default")
      (node (ref "U3") (pin "5") (pinfunction "NC_5") (pintype "unspecified"))
    )
    (net (code "44") (name "unconnected-(U3-VOS_TRIM-Pad1)") (class "Default")
      (node (ref "U3") (pin "1") (pinfunction "VOS_TRIM_1") (pintype "unspecified"))
    )
    (net (code "45") (name "unconnected-(U3-VOS_TRIM-Pad8)") (class "Default")
      (node (ref "U3") (pin "8") (pinfunction "VOS_TRIM_8") (pintype "unspecified"))
    )
    (net (code "46") (name "unconnected-(U6-NC-Pad5)") (class "Default")
      (node (ref "U6") (pin "5") (pinfunction "NC_5") (pintype "unspecified+no_connect"))
    )
    (net (code "47") (name "unconnected-(U6-VOS_TRIM-Pad1)") (class "Default")
      (node (ref "U6") (pin "1") (pinfunction "VOS_TRIM_1") (pintype "unspecified+no_connect"))
    )
    (net (code "48") (name "unconnected-(U6-VOS_TRIM-Pad8)") (class "Default")
      (node (ref "U6") (pin "8") (pinfunction "VOS_TRIM_8") (pintype "unspecified+no_connect"))
    )
    (net (code "49") (name "unconnected-(U7-NC-Pad5)") (class "Default")
      (node (ref "U7") (pin "5") (pinfunction "NC_5") (pintype "unspecified+no_connect"))
    )
    (net (code "50") (name "unconnected-(U7-VOS_TRIM-Pad1)") (class "Default")
      (node (ref "U7") (pin "1") (pinfunction "VOS_TRIM_1") (pintype "unspecified+no_connect"))
    )
    (net (code "51") (name "unconnected-(U7-VOS_TRIM-Pad8)") (class "Default")
      (node (ref "U7") (pin "8") (pinfunction "VOS_TRIM_8") (pintype "unspecified+no_connect"))
    )
  )
)
